# ProPrj_Shell_Controller_2025-04-30.net
KiCad netlist of a schematic drawn in EasyEDA Pro
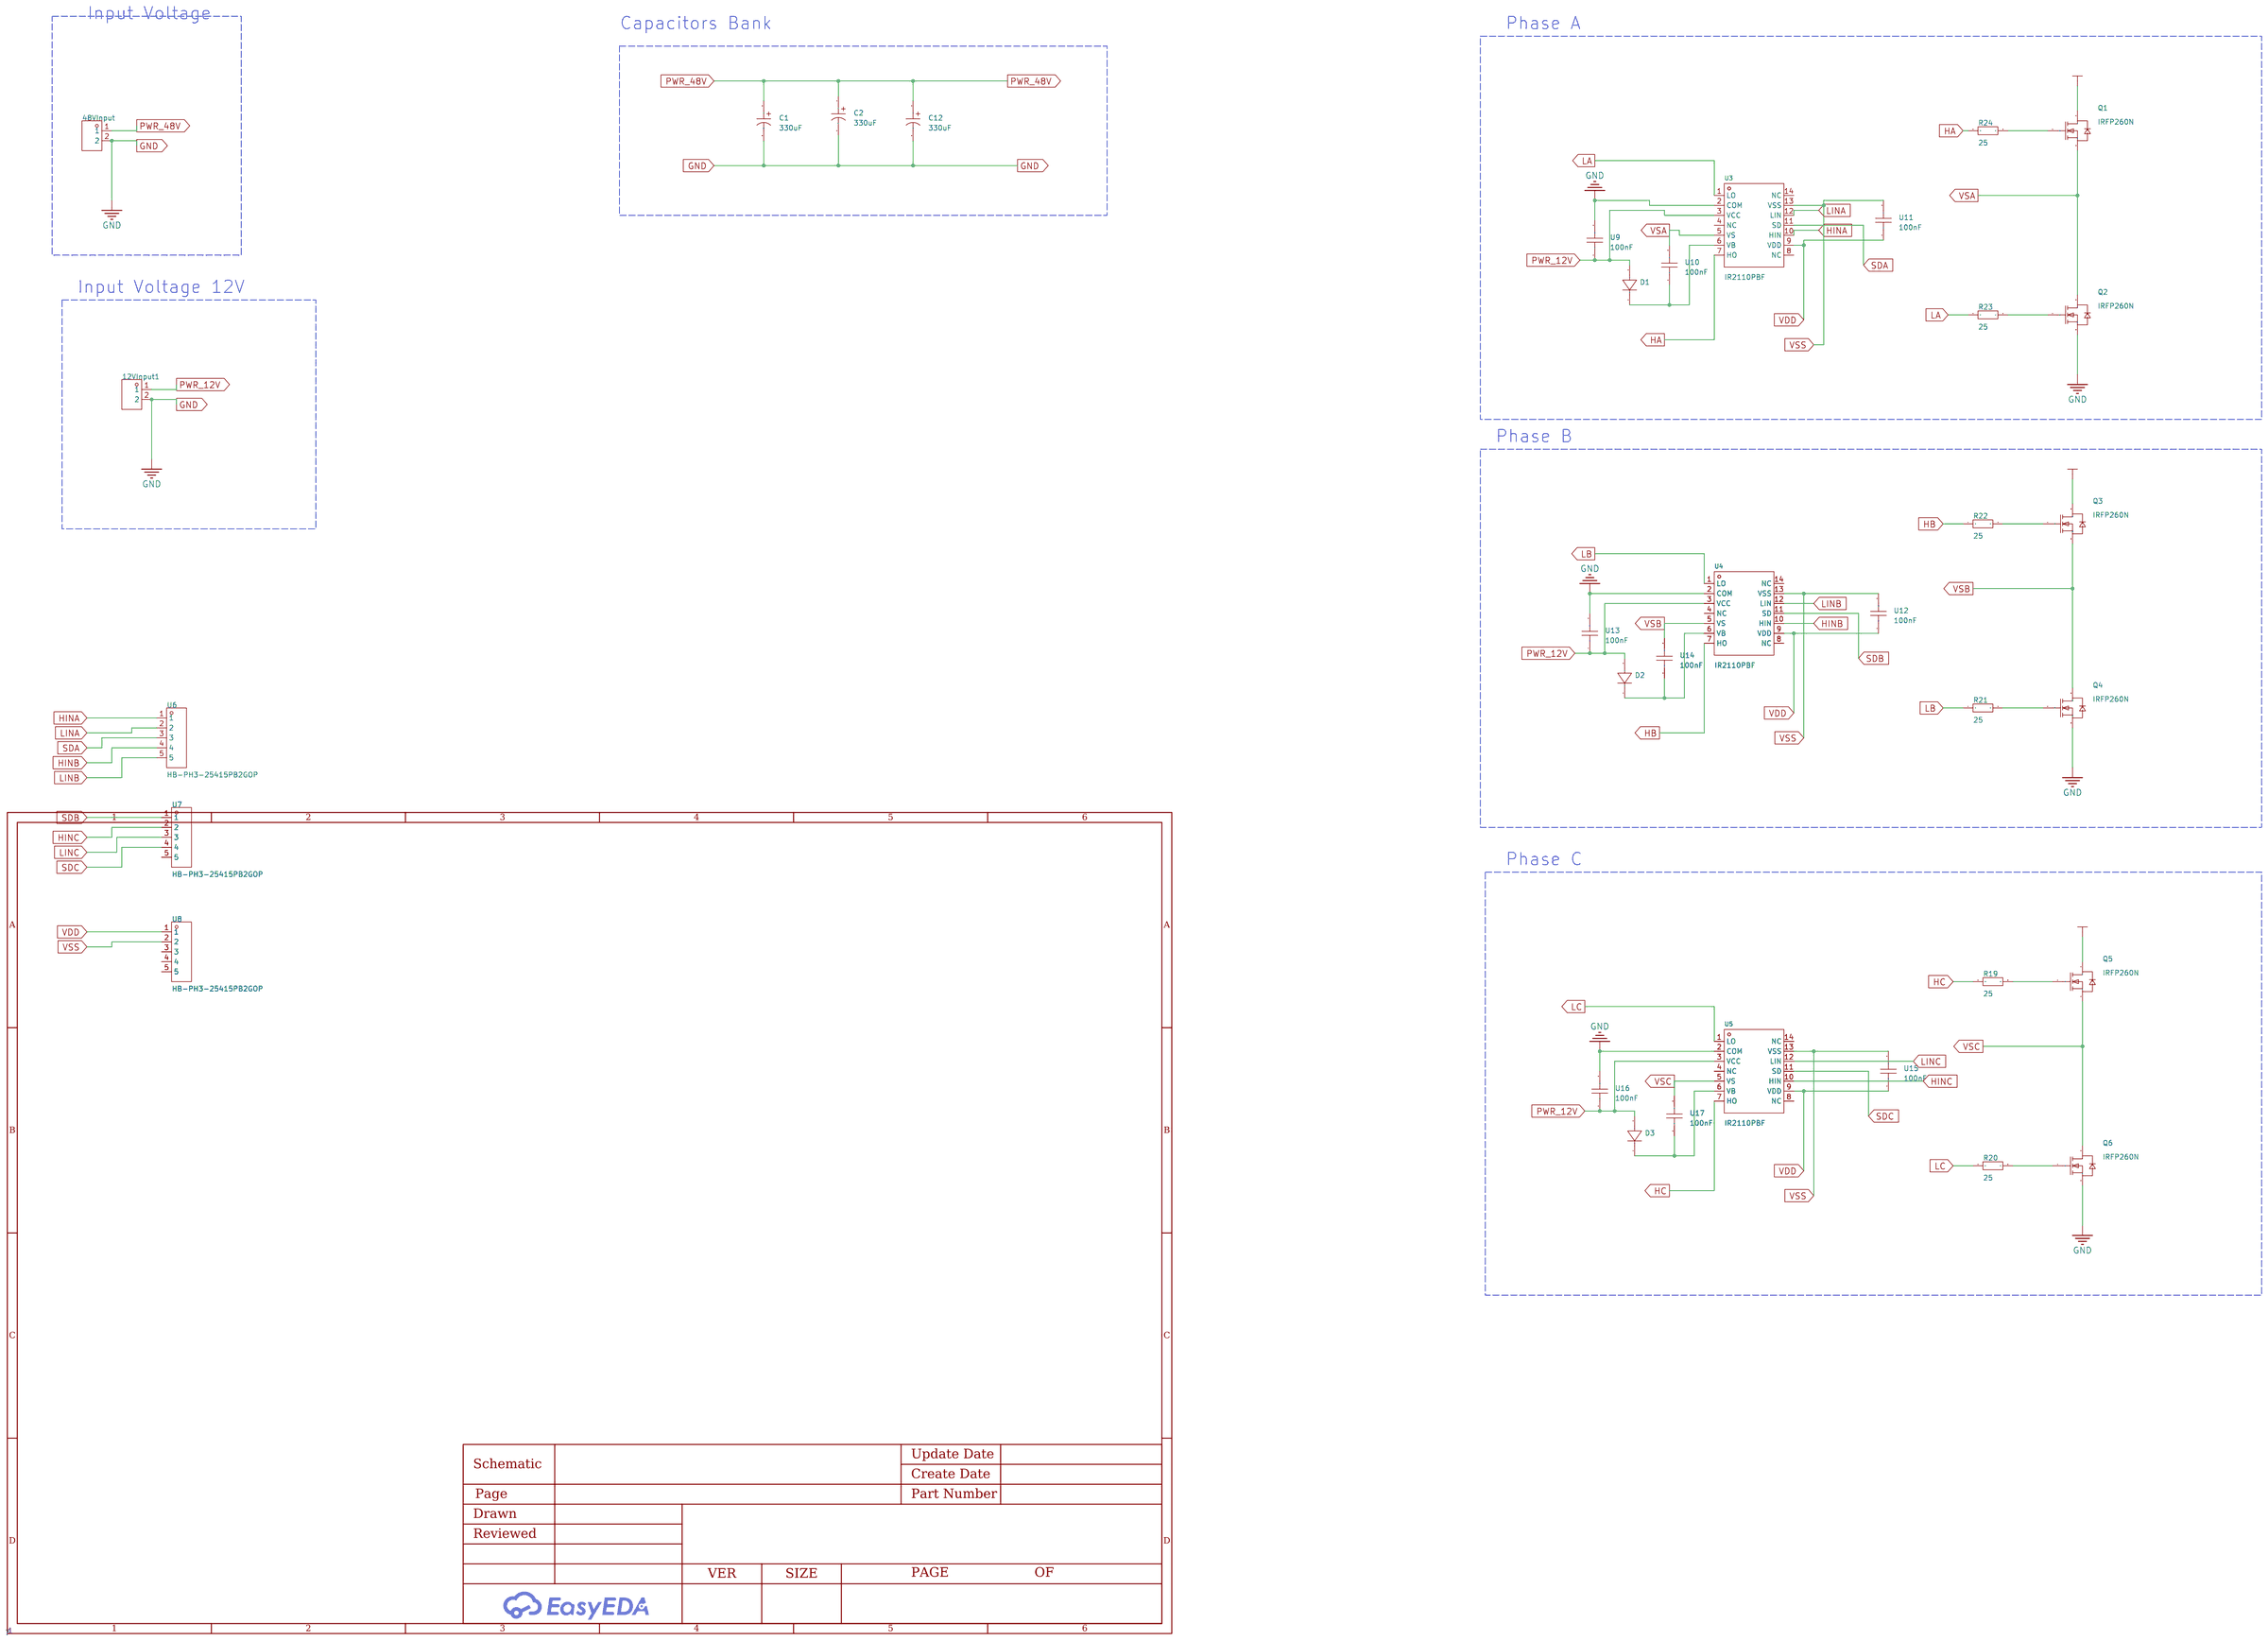
[diagram p0: schematic sheet]

(export (version "E")
  (design (tool "Eeschema 10.0.6"))
  (components
    (comp (ref "12VInput1")
      (value "DBT50G-9.5-2P-BK-P OGC")
      (footprint "easyedapro:CONN-TH_2P-P9.50_DBT50G-9.5-2P")
      (fields (field (name "Manufacturer") "DORABO(地博电气)"))
      (libsource (lib "easyedapro") (part "DBT50G-9.5-2P"))
    )
    (comp (ref "48VInput")
      (value "DBT50G-9.5-2P-BK-P OGC")
      (footprint "easyedapro:CONN-TH_2P-P9.50_DBT50G-9.5-2P")
      (fields (field (name "Manufacturer") "DORABO(地博电气)"))
      (libsource (lib "easyedapro") (part "DBT50G-9.5-2P"))
    )
    (comp (ref "C1")
      (value "330uF")
      (footprint "easyedapro:CAP-TH_BD16.0-P7.50-D0.8-FD")
      (fields
        (field (name "Manufacturer Part") "SHG330UF100V146EC0462")
        (field (name "Manufacturer") "KNSCHA(科尼盛)")
      )
      (libsource (lib "easyedapro") (part "SHG330UF100V146EC0462"))
    )
    (comp (ref "C2")
      (value "330uF")
      (footprint "easyedapro:CAP-TH_BD16.0-P7.50-D0.8-FD")
      (fields
        (field (name "Manufacturer Part") "SHG330UF100V146EC0462")
        (field (name "Manufacturer") "KNSCHA(科尼盛)")
      )
      (libsource (lib "easyedapro") (part "SHG330UF100V146EC0462"))
    )
    (comp (ref "C12")
      (value "330uF")
      (footprint "easyedapro:CAP-TH_BD16.0-P7.50-D0.8-FD")
      (fields
        (field (name "Manufacturer Part") "SHG330UF100V146EC0462")
        (field (name "Manufacturer") "KNSCHA(科尼盛)")
      )
      (libsource (lib "easyedapro") (part "SHG330UF100V146EC0462"))
    )
    (comp (ref "D1")
      (value "~")
      (footprint "easyedapro:DO-41_BD2.4-L4.7-P8.70-D0.9-RD")
      (libsource (lib "easyedapro") (part "D_1N4007"))
    )
    (comp (ref "D2")
      (value "~")
      (footprint "easyedapro:DO-41_BD2.4-L4.7-P8.70-D0.9-RD")
      (libsource (lib "easyedapro") (part "D_1N4007"))
    )
    (comp (ref "D3")
      (value "~")
      (footprint "easyedapro:DO-41_BD2.4-L4.7-P8.70-D0.9-RD")
      (libsource (lib "easyedapro") (part "D_1N4007"))
    )
    (comp (ref "Q1")
      (value "IRFP260N")
      (footprint "easyedapro:TO-247-3_L21.0-W15.9-P5.44-L")
      (fields (field (name "Manufacturer") "minos(迈诺斯)"))
      (libsource (lib "easyedapro") (part "IRFP260N"))
    )
    (comp (ref "Q2")
      (value "IRFP260N")
      (footprint "easyedapro:TO-247-3_L21.0-W15.9-P5.44-L")
      (fields (field (name "Manufacturer") "minos(迈诺斯)"))
      (libsource (lib "easyedapro") (part "IRFP260N"))
    )
    (comp (ref "Q3")
      (value "IRFP260N")
      (footprint "easyedapro:TO-247-3_L21.0-W15.9-P5.44-L")
      (fields (field (name "Manufacturer") "minos(迈诺斯)"))
      (libsource (lib "easyedapro") (part "IRFP260N"))
    )
    (comp (ref "Q4")
      (value "IRFP260N")
      (footprint "easyedapro:TO-247-3_L21.0-W15.9-P5.44-L")
      (fields (field (name "Manufacturer") "minos(迈诺斯)"))
      (libsource (lib "easyedapro") (part "IRFP260N"))
    )
    (comp (ref "Q5")
      (value "IRFP260N")
      (footprint "easyedapro:TO-247-3_L21.0-W15.9-P5.44-L")
      (fields (field (name "Manufacturer") "minos(迈诺斯)"))
      (libsource (lib "easyedapro") (part "IRFP260N"))
    )
    (comp (ref "Q6")
      (value "IRFP260N")
      (footprint "easyedapro:TO-247-3_L21.0-W15.9-P5.44-L")
      (fields (field (name "Manufacturer") "minos(迈诺斯)"))
      (libsource (lib "easyedapro") (part "IRFP260N"))
    )
    (comp (ref "R19") (value "25") (footprint "easyedapro:R0201") (libsource (lib "easyedapro") (part "Res")))
    (comp (ref "R20") (value "25") (footprint "easyedapro:R0201") (libsource (lib "easyedapro") (part "Res")))
    (comp (ref "R21") (value "25") (footprint "easyedapro:R0201") (libsource (lib "easyedapro") (part "Res")))
    (comp (ref "R22") (value "25") (footprint "easyedapro:R0201") (libsource (lib "easyedapro") (part "Res")))
    (comp (ref "R23") (value "25") (footprint "easyedapro:R0201") (libsource (lib "easyedapro") (part "Res")))
    (comp (ref "R24") (value "25") (footprint "easyedapro:R0201") (libsource (lib "easyedapro") (part "Res")))
    (comp (ref "U3")
      (value "IR2110PBF")
      (footprint "easyedapro:DIP-14_L20.0-W7.6-P2.54-LS7.6-BL")
      (fields (field (name "Manufacturer") "Infineon(英飞凌)"))
      (libsource (lib "easyedapro") (part "IR2110PBF_C2967"))
    )
    (comp (ref "U4")
      (value "IR2110PBF")
      (footprint "easyedapro:DIP-14_L20.0-W7.6-P2.54-LS7.6-BL")
      (fields (field (name "Manufacturer") "Infineon(英飞凌)"))
      (libsource (lib "easyedapro") (part "IR2110PBF_C2967"))
    )
    (comp (ref "U5")
      (value "IR2110PBF")
      (footprint "easyedapro:DIP-14_L20.0-W7.6-P2.54-LS7.6-BL")
      (fields (field (name "Manufacturer") "Infineon(英飞凌)"))
      (libsource (lib "easyedapro") (part "IR2110PBF_C2967"))
    )
    (comp (ref "U6")
      (value "HB-PH3-25415PB2GOP")
      (footprint "easyedapro:HDR-TH_5P-P2.54-V-M")
      (fields (field (name "Manufacturer") "HANBO(汉博)"))
      (libsource (lib "easyedapro") (part "HB-PH3-25415PB2GOP"))
    )
    (comp (ref "U7")
      (value "HB-PH3-25415PB2GOP")
      (footprint "easyedapro:HDR-TH_5P-P2.54-V-M")
      (fields (field (name "Manufacturer") "HANBO(汉博)"))
      (libsource (lib "easyedapro") (part "HB-PH3-25415PB2GOP"))
    )
    (comp (ref "U8")
      (value "HB-PH3-25415PB2GOP")
      (footprint "easyedapro:HDR-TH_5P-P2.54-V-M")
      (fields (field (name "Manufacturer") "HANBO(汉博)"))
      (libsource (lib "easyedapro") (part "HB-PH3-25415PB2GOP"))
    )
    (comp (ref "U9")
      (value "100nF")
      (footprint "easyedapro:CAP-TH_L5.5-W4.0-P5.00-D0.5")
      (fields
        (field (name "Manufacturer Part") "Y5P102K1KV16CC0008")
        (field (name "Manufacturer") "KNSCHA(科尼盛)")
      )
      (libsource (lib "easyedapro") (part "Y5P102K1KV16CC0008"))
    )
    (comp (ref "U10")
      (value "100nF")
      (footprint "easyedapro:CAP-TH_L5.5-W4.0-P5.00-D0.5")
      (fields
        (field (name "Manufacturer Part") "Y5P102K1KV16CC0008")
        (field (name "Manufacturer") "KNSCHA(科尼盛)")
      )
      (libsource (lib "easyedapro") (part "Y5P102K1KV16CC0008"))
    )
    (comp (ref "U11")
      (value "100nF")
      (footprint "easyedapro:CAP-TH_L5.5-W4.0-P5.00-D0.5")
      (fields
        (field (name "Manufacturer Part") "Y5P102K1KV16CC0008")
        (field (name "Manufacturer") "KNSCHA(科尼盛)")
      )
      (libsource (lib "easyedapro") (part "Y5P102K1KV16CC0008"))
    )
    (comp (ref "U12")
      (value "100nF")
      (footprint "easyedapro:CAP-TH_L5.5-W4.0-P5.00-D0.5")
      (fields
        (field (name "Manufacturer Part") "Y5P102K1KV16CC0008")
        (field (name "Manufacturer") "KNSCHA(科尼盛)")
      )
      (libsource (lib "easyedapro") (part "Y5P102K1KV16CC0008"))
    )
    (comp (ref "U13")
      (value "100nF")
      (footprint "easyedapro:CAP-TH_L5.5-W4.0-P5.00-D0.5")
      (fields
        (field (name "Manufacturer Part") "Y5P102K1KV16CC0008")
        (field (name "Manufacturer") "KNSCHA(科尼盛)")
      )
      (libsource (lib "easyedapro") (part "Y5P102K1KV16CC0008"))
    )
    (comp (ref "U14")
      (value "100nF")
      (footprint "easyedapro:CAP-TH_L5.5-W4.0-P5.00-D0.5")
      (fields
        (field (name "Manufacturer Part") "Y5P102K1KV16CC0008")
        (field (name "Manufacturer") "KNSCHA(科尼盛)")
      )
      (libsource (lib "easyedapro") (part "Y5P102K1KV16CC0008"))
    )
    (comp (ref "U15")
      (value "100nF")
      (footprint "easyedapro:CAP-TH_L5.5-W4.0-P5.00-D0.5")
      (fields
        (field (name "Manufacturer Part") "Y5P102K1KV16CC0008")
        (field (name "Manufacturer") "KNSCHA(科尼盛)")
      )
      (libsource (lib "easyedapro") (part "Y5P102K1KV16CC0008"))
    )
    (comp (ref "U16")
      (value "100nF")
      (footprint "easyedapro:CAP-TH_L5.5-W4.0-P5.00-D0.5")
      (fields
        (field (name "Manufacturer Part") "Y5P102K1KV16CC0008")
        (field (name "Manufacturer") "KNSCHA(科尼盛)")
      )
      (libsource (lib "easyedapro") (part "Y5P102K1KV16CC0008"))
    )
    (comp (ref "U17")
      (value "100nF")
      (footprint "easyedapro:CAP-TH_L5.5-W4.0-P5.00-D0.5")
      (fields
        (field (name "Manufacturer Part") "Y5P102K1KV16CC0008")
        (field (name "Manufacturer") "KNSCHA(科尼盛)")
      )
      (libsource (lib "easyedapro") (part "Y5P102K1KV16CC0008"))
    )
  )
  (nets
    (net (code "1") (name "GND") (class "Default")
      (node (ref "12VInput1") (pin "2") (pinfunction "2_2") (pintype "unspecified"))
      (node (ref "48VInput") (pin "2") (pinfunction "2_2") (pintype "unspecified"))
      (node (ref "C1") (pin "2") (pinfunction "2_2") (pintype "input"))
      (node (ref "C12") (pin "2") (pinfunction "2_2") (pintype "input"))
      (node (ref "C2") (pin "2") (pinfunction "2_2") (pintype "input"))
      (node (ref "Q2") (pin "3") (pinfunction "S_3") (pintype "unspecified"))
      (node (ref "Q4") (pin "3") (pinfunction "S_3") (pintype "unspecified"))
      (node (ref "Q6") (pin "3") (pinfunction "S_3") (pintype "unspecified"))
      (node (ref "U13") (pin "2") (pinfunction "2_2") (pintype "unspecified"))
      (node (ref "U16") (pin "2") (pinfunction "2_2") (pintype "unspecified"))
      (node (ref "U3") (pin "2") (pinfunction "COM_2") (pintype "input"))
      (node (ref "U4") (pin "2") (pinfunction "COM_2") (pintype "input"))
      (node (ref "U5") (pin "2") (pinfunction "COM_2") (pintype "input"))
      (node (ref "U9") (pin "2") (pinfunction "2_2") (pintype "unspecified"))
    )
    (net (code "2") (name "HA") (class "Default")
      (node (ref "R24") (pin "1") (pinfunction "1_1") (pintype "input"))
      (node (ref "U3") (pin "7") (pinfunction "HO_7") (pintype "input"))
    )
    (net (code "3") (name "HB") (class "Default")
      (node (ref "R22") (pin "1") (pinfunction "1_1") (pintype "input"))
      (node (ref "U4") (pin "7") (pinfunction "HO_7") (pintype "input"))
    )
    (net (code "4") (name "HC") (class "Default")
      (node (ref "R19") (pin "1") (pinfunction "1_1") (pintype "input"))
      (node (ref "U5") (pin "7") (pinfunction "HO_7") (pintype "input"))
    )
    (net (code "5") (name "HINA") (class "Default")
      (node (ref "U3") (pin "10") (pinfunction "HIN_10") (pintype "input"))
      (node (ref "U6") (pin "1") (pinfunction "1_1") (pintype "unspecified"))
    )
    (net (code "6") (name "HINB") (class "Default")
      (node (ref "U4") (pin "10") (pinfunction "HIN_10") (pintype "input"))
      (node (ref "U6") (pin "4") (pinfunction "4_4") (pintype "unspecified"))
    )
    (net (code "7") (name "HINC") (class "Default")
      (node (ref "U5") (pin "10") (pinfunction "HIN_10") (pintype "input"))
      (node (ref "U7") (pin "2") (pinfunction "2_2") (pintype "unspecified"))
    )
    (net (code "8") (name "LA") (class "Default")
      (node (ref "R23") (pin "1") (pinfunction "1_1") (pintype "input"))
      (node (ref "U3") (pin "1") (pinfunction "LO_1") (pintype "input"))
    )
    (net (code "9") (name "LB") (class "Default")
      (node (ref "R21") (pin "1") (pinfunction "1_1") (pintype "input"))
      (node (ref "U4") (pin "1") (pinfunction "LO_1") (pintype "input"))
    )
    (net (code "10") (name "LC") (class "Default")
      (node (ref "R20") (pin "1") (pinfunction "1_1") (pintype "input"))
      (node (ref "U5") (pin "1") (pinfunction "LO_1") (pintype "input"))
    )
    (net (code "11") (name "LINA") (class "Default")
      (node (ref "U3") (pin "12") (pinfunction "LIN_12") (pintype "input"))
      (node (ref "U6") (pin "2") (pinfunction "2_2") (pintype "unspecified"))
    )
    (net (code "12") (name "LINB") (class "Default")
      (node (ref "U4") (pin "12") (pinfunction "LIN_12") (pintype "input"))
      (node (ref "U6") (pin "5") (pinfunction "5_5") (pintype "unspecified"))
    )
    (net (code "13") (name "LINC") (class "Default")
      (node (ref "U5") (pin "12") (pinfunction "LIN_12") (pintype "input"))
      (node (ref "U7") (pin "3") (pinfunction "3_3") (pintype "unspecified"))
    )
    (net (code "14") (name "Net-(D1-K)") (class "Default")
      (node (ref "D1") (pin "1") (pinfunction "K_1") (pintype "input"))
      (node (ref "U10") (pin "1") (pinfunction "1_1") (pintype "unspecified"))
      (node (ref "U3") (pin "6") (pinfunction "VB_6") (pintype "input"))
    )
    (net (code "15") (name "Net-(D2-K)") (class "Default")
      (node (ref "D2") (pin "1") (pinfunction "K_1") (pintype "input"))
      (node (ref "U14") (pin "1") (pinfunction "1_1") (pintype "unspecified"))
      (node (ref "U4") (pin "6") (pinfunction "VB_6") (pintype "input"))
    )
    (net (code "16") (name "Net-(D3-K)") (class "Default")
      (node (ref "D3") (pin "1") (pinfunction "K_1") (pintype "input"))
      (node (ref "U17") (pin "1") (pinfunction "1_1") (pintype "unspecified"))
      (node (ref "U5") (pin "6") (pinfunction "VB_6") (pintype "input"))
    )
    (net (code "17") (name "Net-(Q1-G)") (class "Default")
      (node (ref "Q1") (pin "1") (pinfunction "G_1") (pintype "unspecified"))
      (node (ref "R24") (pin "2") (pinfunction "2_2") (pintype "input"))
    )
    (net (code "18") (name "Net-(Q2-G)") (class "Default")
      (node (ref "Q2") (pin "1") (pinfunction "G_1") (pintype "unspecified"))
      (node (ref "R23") (pin "2") (pinfunction "2_2") (pintype "input"))
    )
    (net (code "19") (name "Net-(Q3-G)") (class "Default")
      (node (ref "Q3") (pin "1") (pinfunction "G_1") (pintype "unspecified"))
      (node (ref "R22") (pin "2") (pinfunction "2_2") (pintype "input"))
    )
    (net (code "20") (name "Net-(Q4-G)") (class "Default")
      (node (ref "Q4") (pin "1") (pinfunction "G_1") (pintype "unspecified"))
      (node (ref "R21") (pin "2") (pinfunction "2_2") (pintype "input"))
    )
    (net (code "21") (name "Net-(Q5-G)") (class "Default")
      (node (ref "Q5") (pin "1") (pinfunction "G_1") (pintype "unspecified"))
      (node (ref "R19") (pin "2") (pinfunction "2_2") (pintype "input"))
    )
    (net (code "22") (name "Net-(Q6-G)") (class "Default")
      (node (ref "Q6") (pin "1") (pinfunction "G_1") (pintype "unspecified"))
      (node (ref "R20") (pin "2") (pinfunction "2_2") (pintype "input"))
    )
    (net (code "23") (name "PWR_12V") (class "Default")
      (node (ref "12VInput1") (pin "1") (pinfunction "1_1") (pintype "unspecified"))
      (node (ref "D1") (pin "2") (pinfunction "A_2") (pintype "input"))
      (node (ref "D2") (pin "2") (pinfunction "A_2") (pintype "input"))
      (node (ref "D3") (pin "2") (pinfunction "A_2") (pintype "input"))
      (node (ref "U13") (pin "1") (pinfunction "1_1") (pintype "unspecified"))
      (node (ref "U16") (pin "1") (pinfunction "1_1") (pintype "unspecified"))
      (node (ref "U3") (pin "3") (pinfunction "VCC_3") (pintype "input"))
      (node (ref "U4") (pin "3") (pinfunction "VCC_3") (pintype "input"))
      (node (ref "U5") (pin "3") (pinfunction "VCC_3") (pintype "input"))
      (node (ref "U9") (pin "1") (pinfunction "1_1") (pintype "unspecified"))
    )
    (net (code "24") (name "PWR_48V") (class "Default")
      (node (ref "48VInput") (pin "1") (pinfunction "1_1") (pintype "unspecified"))
      (node (ref "C1") (pin "1") (pinfunction "1_1") (pintype "input"))
      (node (ref "C12") (pin "1") (pinfunction "1_1") (pintype "input"))
      (node (ref "C2") (pin "1") (pinfunction "1_1") (pintype "input"))
      (node (ref "Q1") (pin "2") (pinfunction "D_2") (pintype "unspecified"))
      (node (ref "Q3") (pin "2") (pinfunction "D_2") (pintype "unspecified"))
      (node (ref "Q5") (pin "2") (pinfunction "D_2") (pintype "unspecified"))
    )
    (net (code "25") (name "SDA") (class "Default")
      (node (ref "U3") (pin "11") (pinfunction "SD_11") (pintype "input"))
      (node (ref "U6") (pin "3") (pinfunction "3_3") (pintype "unspecified"))
    )
    (net (code "26") (name "SDB") (class "Default")
      (node (ref "U4") (pin "11") (pinfunction "SD_11") (pintype "input"))
      (node (ref "U7") (pin "1") (pinfunction "1_1") (pintype "unspecified"))
    )
    (net (code "27") (name "SDC") (class "Default")
      (node (ref "U5") (pin "11") (pinfunction "SD_11") (pintype "input"))
      (node (ref "U7") (pin "4") (pinfunction "4_4") (pintype "unspecified"))
    )
    (net (code "28") (name "VDD") (class "Default")
      (node (ref "U11") (pin "1") (pinfunction "1_1") (pintype "unspecified"))
      (node (ref "U12") (pin "1") (pinfunction "1_1") (pintype "unspecified"))
      (node (ref "U15") (pin "1") (pinfunction "1_1") (pintype "unspecified"))
      (node (ref "U3") (pin "9") (pinfunction "VDD_9") (pintype "input"))
      (node (ref "U4") (pin "9") (pinfunction "VDD_9") (pintype "input"))
      (node (ref "U5") (pin "9") (pinfunction "VDD_9") (pintype "input"))
      (node (ref "U8") (pin "1") (pinfunction "1_1") (pintype "unspecified"))
    )
    (net (code "29") (name "VSA") (class "Default")
      (node (ref "Q1") (pin "3") (pinfunction "S_3") (pintype "unspecified"))
      (node (ref "Q2") (pin "2") (pinfunction "D_2") (pintype "unspecified"))
      (node (ref "U10") (pin "2") (pinfunction "2_2") (pintype "unspecified"))
      (node (ref "U3") (pin "5") (pinfunction "VS_5") (pintype "input"))
    )
    (net (code "30") (name "VSB") (class "Default")
      (node (ref "Q3") (pin "3") (pinfunction "S_3") (pintype "unspecified"))
      (node (ref "Q4") (pin "2") (pinfunction "D_2") (pintype "unspecified"))
      (node (ref "U14") (pin "2") (pinfunction "2_2") (pintype "unspecified"))
      (node (ref "U4") (pin "5") (pinfunction "VS_5") (pintype "input"))
    )
    (net (code "31") (name "VSC") (class "Default")
      (node (ref "Q5") (pin "3") (pinfunction "S_3") (pintype "unspecified"))
      (node (ref "Q6") (pin "2") (pinfunction "D_2") (pintype "unspecified"))
      (node (ref "U17") (pin "2") (pinfunction "2_2") (pintype "unspecified"))
      (node (ref "U5") (pin "5") (pinfunction "VS_5") (pintype "input"))
    )
    (net (code "32") (name "VSS") (class "Default")
      (node (ref "U11") (pin "2") (pinfunction "2_2") (pintype "unspecified"))
      (node (ref "U12") (pin "2") (pinfunction "2_2") (pintype "unspecified"))
      (node (ref "U15") (pin "2") (pinfunction "2_2") (pintype "unspecified"))
      (node (ref "U3") (pin "13") (pinfunction "VSS_13") (pintype "input"))
      (node (ref "U4") (pin "13") (pinfunction "VSS_13") (pintype "input"))
      (node (ref "U5") (pin "13") (pinfunction "VSS_13") (pintype "input"))
      (node (ref "U8") (pin "2") (pinfunction "2_2") (pintype "unspecified"))
    )
    (net (code "33") (name "unconnected-(U3-NC-Pad4)") (class "Default")
      (node (ref "U3") (pin "4") (pinfunction "NC_4") (pintype "input"))
    )
    (net (code "34") (name "unconnected-(U3-NC-Pad8)") (class "Default")
      (node (ref "U3") (pin "8") (pinfunction "NC_8") (pintype "input"))
    )
    (net (code "35") (name "unconnected-(U3-NC-Pad14)") (class "Default")
      (node (ref "U3") (pin "14") (pinfunction "NC_14") (pintype "input"))
    )
    (net (code "36") (name "unconnected-(U4-NC-Pad4)") (class "Default")
      (node (ref "U4") (pin "4") (pinfunction "NC_4") (pintype "input"))
    )
    (net (code "37") (name "unconnected-(U4-NC-Pad8)") (class "Default")
      (node (ref "U4") (pin "8") (pinfunction "NC_8") (pintype "input"))
    )
    (net (code "38") (name "unconnected-(U4-NC-Pad14)") (class "Default")
      (node (ref "U4") (pin "14") (pinfunction "NC_14") (pintype "input"))
    )
    (net (code "39") (name "unconnected-(U5-NC-Pad4)") (class "Default")
      (node (ref "U5") (pin "4") (pinfunction "NC_4") (pintype "input"))
    )
    (net (code "40") (name "unconnected-(U5-NC-Pad8)") (class "Default")
      (node (ref "U5") (pin "8") (pinfunction "NC_8") (pintype "input"))
    )
    (net (code "41") (name "unconnected-(U5-NC-Pad14)") (class "Default")
      (node (ref "U5") (pin "14") (pinfunction "NC_14") (pintype "input"))
    )
    (net (code "42") (name "unconnected-(U7-Pad5)") (class "Default")
      (node (ref "U7") (pin "5") (pinfunction "5_5") (pintype "unspecified"))
    )
    (net (code "43") (name "unconnected-(U8-Pad3)") (class "Default")
      (node (ref "U8") (pin "3") (pinfunction "3_3") (pintype "unspecified"))
    )
    (net (code "44") (name "unconnected-(U8-Pad4)") (class "Default")
      (node (ref "U8") (pin "4") (pinfunction "4_4") (pintype "unspecified"))
    )
    (net (code "45") (name "unconnected-(U8-Pad5)") (class "Default")
      (node (ref "U8") (pin "5") (pinfunction "5_5") (pintype "unspecified"))
    )
  )
)
